# main.net
KiCad netlist of a schematic drawn in Altium Designer
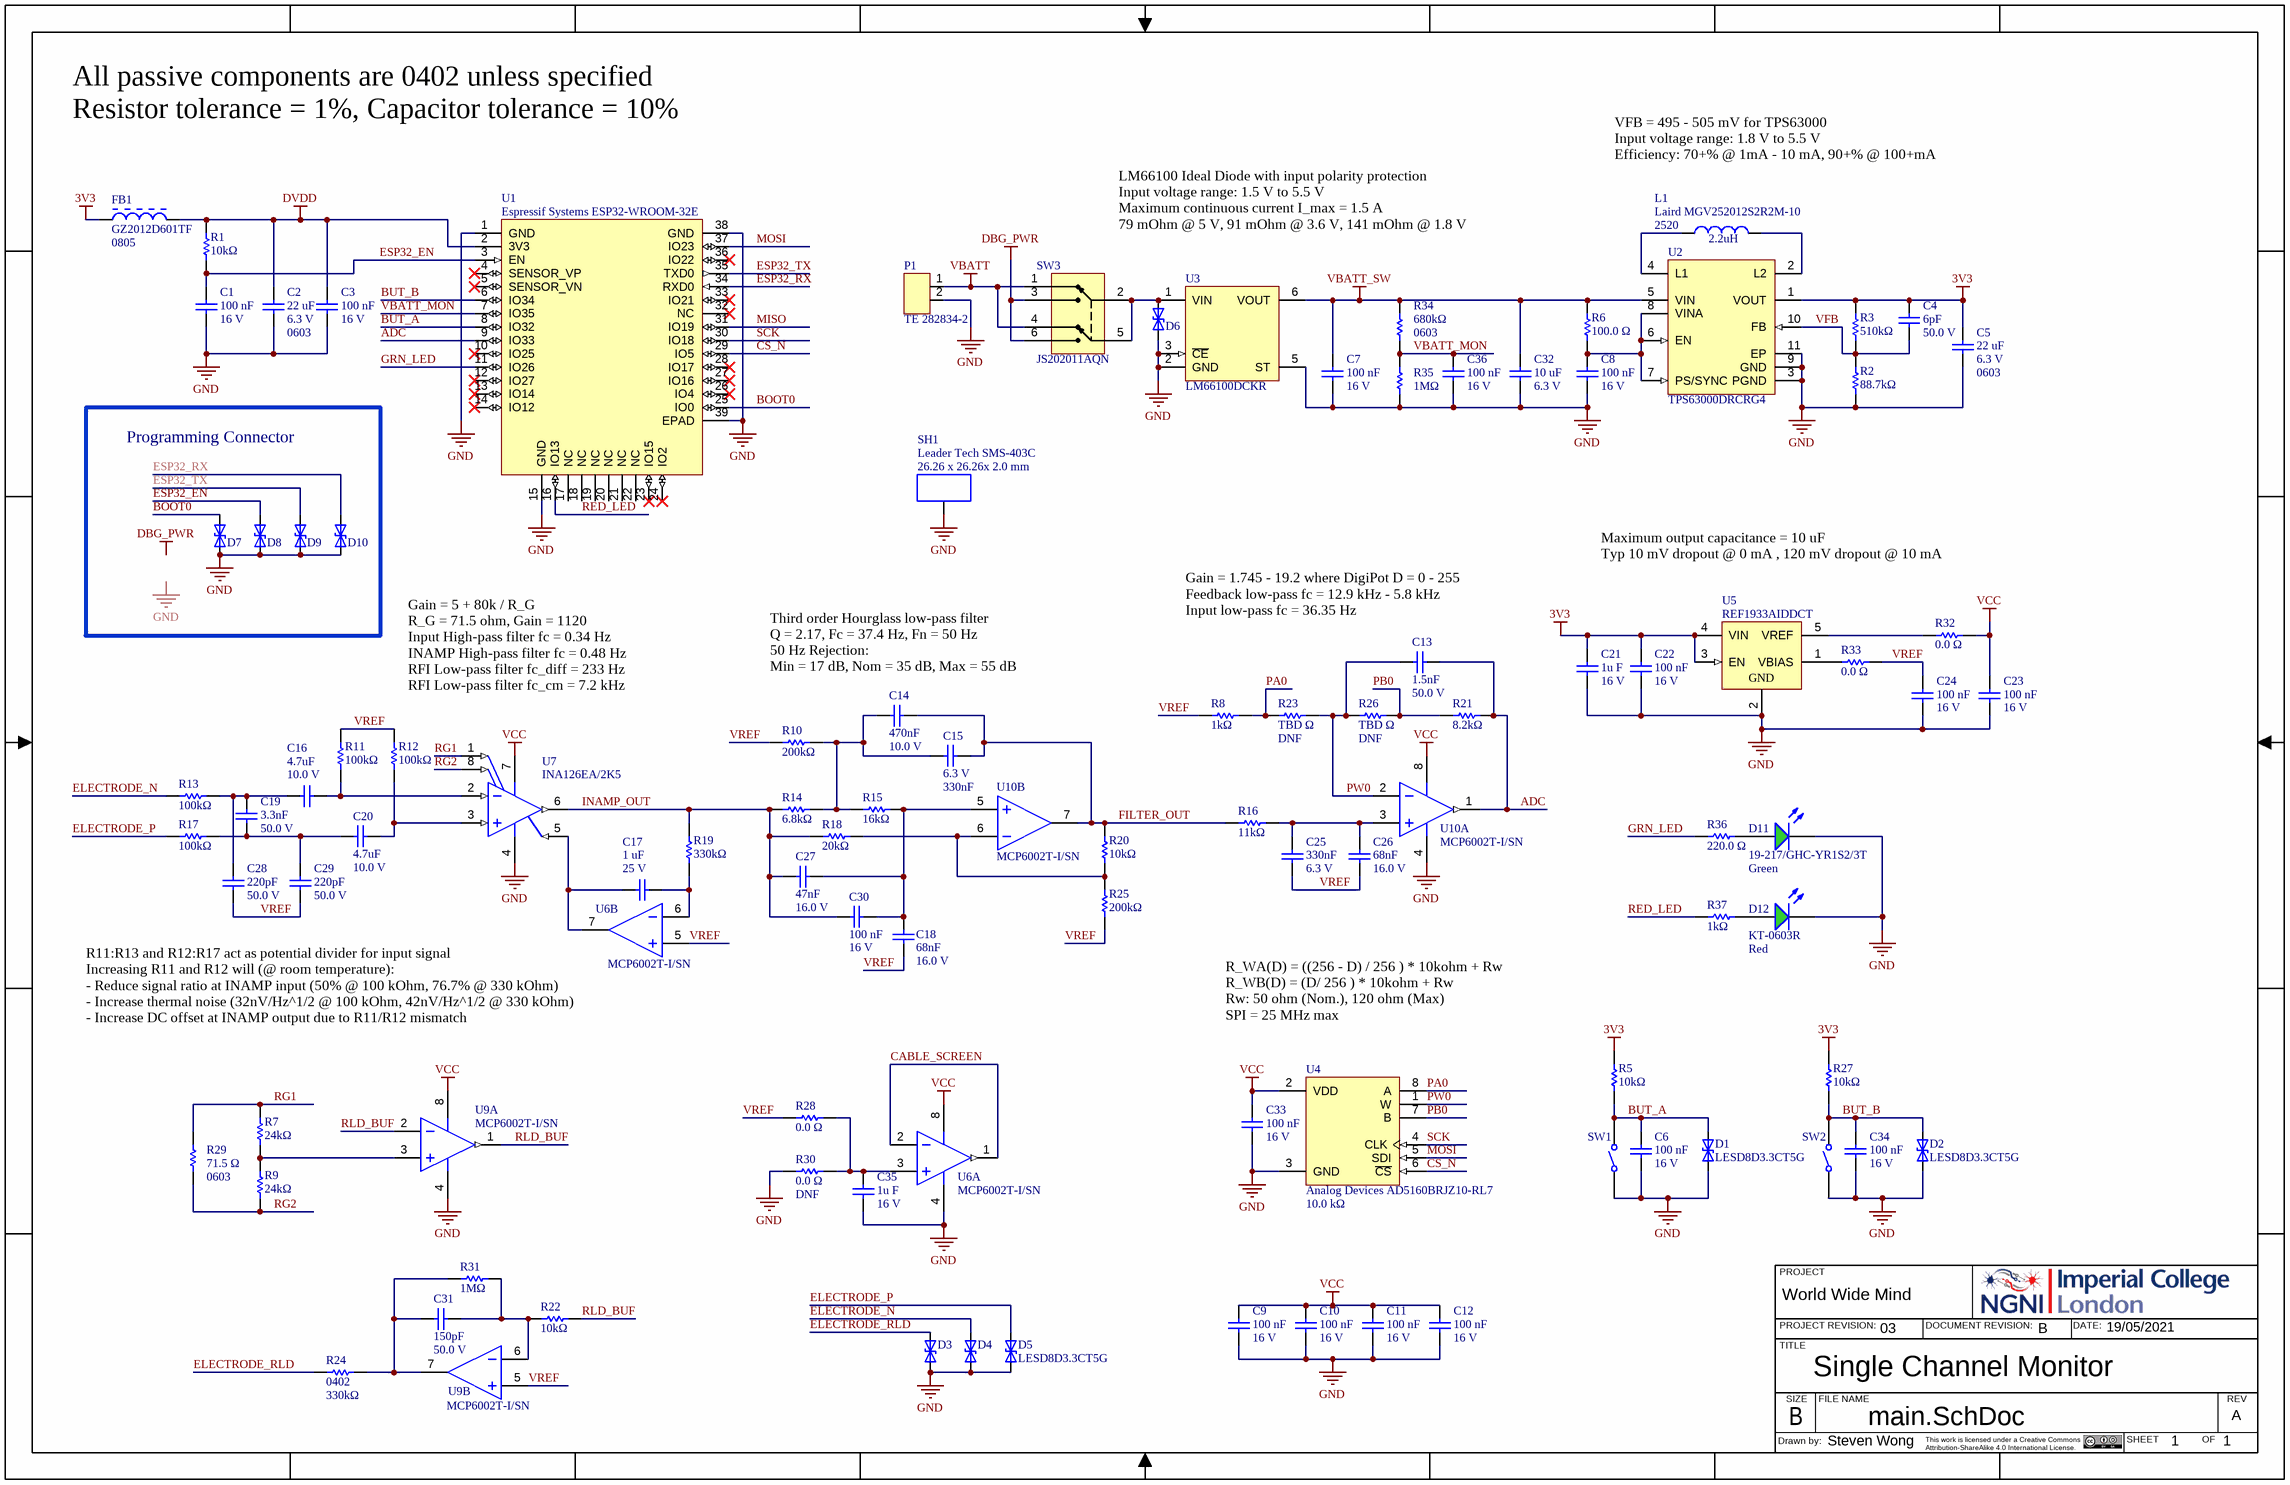
[diagram p0: main.SchDoc]

(export (version "E")
  (design (tool "Eeschema 10.0.6"))
  (components
    (comp (ref "C1")
      (value "100nF")
      (footprint "CAPC1005X56X25NL10T15")
      (description "Ceramic capacitor SMD-0402 100nF /16V X7R# K +-10%, Samsung, RoHS")
      (fields
        (field (name "CAPACITANCE") "100 nF")
        (field (name "VOLTAGE RATING") "16 V")
        (field (name "LCSC PART #") "C1525")
      )
      (libsource (lib "CommunityVault") (part "CMP-bf2276a55d9a60e5-19"))
    )
    (comp (ref "C2")
      (value "Murata GRM188R60G226MEA0L")
      (footprint "CAPC1608X90X35NL10T15")
      (description "Cap Ceramic 22uF 6.3V X5R 20% SMD 0603 85C Embossed T/R")
      (fields
        (field (name "CAPACITANCE") "22 uF")
        (field (name "VOLTAGE RATING (DC)") "6.3 V")
        (field (name "MANUFACTURER PART NUMBER") "GRM188R60G226MEA0L")
        (field (name "PACKAGE") "0603")
        (field (name "LCSC PART #") "C59461")
      )
      (libsource (lib "CommunityVault") (part "CMP-122043-3"))
    )
    (comp (ref "C3")
      (value "100nF")
      (footprint "CAPC1005X56X25NL10T15")
      (description "Ceramic capacitor SMD-0402 100nF /16V X7R# K +-10%, Samsung, RoHS")
      (fields
        (field (name "CAPACITANCE") "100 nF")
        (field (name "VOLTAGE RATING") "16 V")
        (field (name "LCSC PART #") "C1525")
      )
      (libsource (lib "CommunityVault") (part "CMP-bf2276a55d9a60e5-19"))
    )
    (comp (ref "C4")
      (value "AVX Interconnect / Elco 04025A6R0DAT2A")
      (footprint "CAPC1005X60X25NL10T15")
      (description "Multilayer Ceramic Capacitors MLCC - SMD/SMT 50volts 6pF C0G")
      (fields
        (field (name "CAPACITANCE") "6pF")
        (field (name "VOLTAGE RATING (DC)") "50.0 V")
        (field (name "MANUFACTURER PART NUMBER") "04025A6R0DAT2A")
        (field (name "LCSC PART #") "C30274")
      )
      (libsource (lib "CommunityVault") (part "CMP-173346-2"))
    )
    (comp (ref "C5")
      (value "Murata GRM188R60G226MEA0L")
      (footprint "CAPC1608X90X35NL10T15")
      (description "Cap Ceramic 22uF 6.3V X5R 20% SMD 0603 85C Embossed T/R")
      (fields
        (field (name "CAPACITANCE") "22 uF")
        (field (name "VOLTAGE RATING (DC)") "6.3 V")
        (field (name "MANUFACTURER PART NUMBER") "GRM188R60G226MEA0L")
        (field (name "PACKAGE") "0603")
        (field (name "LCSC PART #") "C59461")
      )
      (libsource (lib "CommunityVault") (part "CMP-122043-3"))
    )
    (comp (ref "C6")
      (value "100nF")
      (footprint "CAPC1005X56X25NL10T15")
      (description "Ceramic capacitor SMD-0402 100nF /16V X7R# K +-10%, Samsung, RoHS")
      (fields
        (field (name "CAPACITANCE") "100 nF")
        (field (name "VOLTAGE RATING") "16 V")
        (field (name "LCSC PART #") "C1525")
      )
      (libsource (lib "CommunityVault") (part "CMP-bf2276a55d9a60e5-19"))
    )
    (comp (ref "C7")
      (value "100nF")
      (footprint "CAPC1005X56X25NL10T15")
      (description "Ceramic capacitor SMD-0402 100nF /16V X7R# K +-10%, Samsung, RoHS")
      (fields
        (field (name "CAPACITANCE") "100 nF")
        (field (name "VOLTAGE RATING") "16 V")
        (field (name "LCSC PART #") "C1525")
      )
      (libsource (lib "CommunityVault") (part "CMP-bf2276a55d9a60e5-19"))
    )
    (comp (ref "C8")
      (value "100nF")
      (footprint "CAPC1005X56X25NL10T15")
      (description "Ceramic capacitor SMD-0402 100nF /16V X7R# K +-10%, Samsung, RoHS")
      (fields
        (field (name "CAPACITANCE") "100 nF")
        (field (name "VOLTAGE RATING") "16 V")
        (field (name "LCSC PART #") "C1525")
      )
      (libsource (lib "CommunityVault") (part "CMP-bf2276a55d9a60e5-19"))
    )
    (comp (ref "C9")
      (value "100nF")
      (footprint "CAPC1005X56X25NL10T15")
      (description "Ceramic capacitor SMD-0402 100nF /16V X7R# K +-10%, Samsung, RoHS")
      (fields
        (field (name "CAPACITANCE") "100 nF")
        (field (name "VOLTAGE RATING") "16 V")
        (field (name "LCSC PART #") "C1525")
      )
      (libsource (lib "CommunityVault") (part "CMP-bf2276a55d9a60e5-19"))
    )
    (comp (ref "C10")
      (value "100nF")
      (footprint "CAPC1005X56X25NL10T15")
      (description "Ceramic capacitor SMD-0402 100nF /16V X7R# K +-10%, Samsung, RoHS")
      (fields
        (field (name "CAPACITANCE") "100 nF")
        (field (name "VOLTAGE RATING") "16 V")
        (field (name "LCSC PART #") "C1525")
      )
      (libsource (lib "CommunityVault") (part "CMP-bf2276a55d9a60e5-19"))
    )
    (comp (ref "C11")
      (value "100nF")
      (footprint "CAPC1005X56X25NL10T15")
      (description "Ceramic capacitor SMD-0402 100nF /16V X7R# K +-10%, Samsung, RoHS")
      (fields
        (field (name "CAPACITANCE") "100 nF")
        (field (name "VOLTAGE RATING") "16 V")
        (field (name "LCSC PART #") "C1525")
      )
      (libsource (lib "CommunityVault") (part "CMP-bf2276a55d9a60e5-19"))
    )
    (comp (ref "C12")
      (value "100nF")
      (footprint "CAPC1005X56X25NL10T15")
      (description "Ceramic capacitor SMD-0402 100nF /16V X7R# K +-10%, Samsung, RoHS")
      (fields
        (field (name "CAPACITANCE") "100 nF")
        (field (name "VOLTAGE RATING") "16 V")
        (field (name "LCSC PART #") "C1525")
      )
      (libsource (lib "CommunityVault") (part "CMP-bf2276a55d9a60e5-19"))
    )
    (comp (ref "C13")
      (value "AVX Interconnect / Elco 04025C152KAT2A")
      (footprint "CAPC1005X56X25NL10T15")
      (description "Cap Ceramic 0.0015uF 50V X7R 10% SMD 0402 125C Paper T/R")
      (fields
        (field (name "MANUFACTURER PART NUMBER") "04025C152KAT2A")
        (field (name "CAPACITANCE") "1.5nF")
        (field (name "VOLTAGE RATING (DC)") "50.0 V")
        (field (name "LCSC PART #") "C23967")
      )
      (libsource (lib "CommunityVault") (part "CMP-126494-2"))
    )
    (comp (ref "C14")
      (value "AVX Interconnect / Elco 0402ZD474KAT2A")
      (footprint "CAPC1005X56X25NL10T15")
      (description "Multilayer Ceramic Capacitors MLCC - SMD/SMT 10volts 0.47uF 10% X5R")
      (fields
        (field (name "MANUFACTURER PART NUMBER") "0402ZD474KAT2A")
        (field (name "CAPACITANCE") "470nF")
        (field (name "VOLTAGE RATING (DC)") "10.0 V")
        (field (name "LCSC PART #") "C47339")
      )
      (libsource (lib "CommunityVault") (part "CMP-4106702-2"))
    )
    (comp (ref "C15")
      (value "CL05A334KQ5NNNC")
      (footprint "CAPC1005X55X25NL05T10")
      (description "CAP CER 0.33UF 10V 10% X5R 0402")
      (fields
        (field (name "VOLTAGE RATING (DC)") "6.3 V")
        (field (name "CAPACITANCE") "330nF")
        (field (name "LCSC PART #") "C307420")
      )
      (libsource (lib "CommunityVault") (part "CMP-119553-3"))
    )
    (comp (ref "C16")
      (value "CL05A475MP5NRNC")
      (footprint "CAPC1005X56X25NL10T15")
      (description "T&R / COMMERCIAL CHIP")
      (fields
        (field (name "CAPACITANCE") "4.7uF")
        (field (name "VOLTAGE RATING (DC)") "10.0 V")
        (field (name "LCSC PART #") "C23733")
      )
      (libsource (lib "CommunityVault") (part "CMP-19563753-2"))
    )
    (comp (ref "C17")
      (value "Samsung CL05A105KA5NQNC")
      (footprint "PCB-515da9ytrm2wahx6tw11-1")
      (description "Cap Ceramic 1uF 25V X5R 10% SMD 0402 85°C Cardboard T/R")
      (fields
        (field (name "VOLTAGE RATING (DC)") "25 V")
        (field (name "CAPACITANCE") "1 uF")
        (field (name "MANUFACTURER PART NUMBER") "CL05A105KA5NQNC")
        (field (name "LCSC PART #") "C52923")
      )
      (libsource (lib "CommunityVault") (part "CMP-8f214705328650e6-4"))
    )
    (comp (ref "C18")
      (value "Kemet C0402C683K4RACTU")
      (footprint "CAPC1005X55X30NL05T10")
      (description "CAP CER 0.068UF 16V 10% X7R 0402")
      (fields
        (field (name "CAPACITANCE") "68nF")
        (field (name "VOLTAGE RATING (DC)") "16.0 V")
        (field (name "MANUFACTURER PART NUMBER") "C0402C683K4RACTU")
        (field (name "LCSC PART #") "C12529")
      )
      (libsource (lib "CommunityVault") (part "CMP-124577-2"))
    )
    (comp (ref "C19")
      (value "AVX Interconnect / Elco 04025C332KAT2A")
      (footprint "CAPC1005X56X25NL10T15")
      (description "AVX   04025C332KAT2A   CAP, MLCC, X7R, 3.3NF, 50V, 0402")
      (fields
        (field (name "CAPACITANCE") "3.3nF")
        (field (name "VOLTAGE RATING (DC)") "50.0 V")
        (field (name "MANUFACTURER PART NUMBER") "04025C332KAT2A")
        (field (name "LCSC PART #") "C26404")
      )
      (libsource (lib "CommunityVault") (part "CMP-128367-2"))
    )
    (comp (ref "C20")
      (value "CL05A475MP5NRNC")
      (footprint "CAPC1005X56X25NL10T15")
      (description "T&R / COMMERCIAL CHIP")
      (fields
        (field (name "CAPACITANCE") "4.7uF")
        (field (name "VOLTAGE RATING (DC)") "10.0 V")
        (field (name "LCSC PART #") "C23733")
      )
      (libsource (lib "CommunityVault") (part "CMP-19563753-2"))
    )
    (comp (ref "C21")
      (value "Murata GRM155R61C105KA12D")
      (footprint "CAPC1005X55X25NL05T10")
      (description "Cap Ceramic 1uF 16V X5R 10% SMD 0402 85C Paper T/R")
      (fields
        (field (name "CAPACITANCE") "1u F")
        (field (name "VOLTAGE RATING (DC)") "16 V")
        (field (name "MANUFACTURER PART NUMBER") "GRM155R61C105KA12D")
        (field (name "LCSC PART #") "C52923")
      )
      (libsource (lib "CommunityVault") (part "CMP-7562325-2"))
    )
    (comp (ref "C22")
      (value "100nF")
      (footprint "CAPC1005X56X25NL10T15")
      (description "Ceramic capacitor SMD-0402 100nF /16V X7R# K +-10%, Samsung, RoHS")
      (fields
        (field (name "CAPACITANCE") "100 nF")
        (field (name "VOLTAGE RATING") "16 V")
        (field (name "LCSC PART #") "C1525")
      )
      (libsource (lib "CommunityVault") (part "CMP-bf2276a55d9a60e5-19"))
    )
    (comp (ref "C23")
      (value "100nF")
      (footprint "CAPC1005X56X25NL10T15")
      (description "Ceramic capacitor SMD-0402 100nF /16V X7R# K +-10%, Samsung, RoHS")
      (fields
        (field (name "CAPACITANCE") "100 nF")
        (field (name "VOLTAGE RATING") "16 V")
        (field (name "LCSC PART #") "C1525")
      )
      (libsource (lib "CommunityVault") (part "CMP-bf2276a55d9a60e5-19"))
    )
    (comp (ref "C24")
      (value "100nF")
      (footprint "CAPC1005X56X25NL10T15")
      (description "Ceramic capacitor SMD-0402 100nF /16V X7R# K +-10%, Samsung, RoHS")
      (fields
        (field (name "CAPACITANCE") "100 nF")
        (field (name "VOLTAGE RATING") "16 V")
        (field (name "LCSC PART #") "C1525")
      )
      (libsource (lib "CommunityVault") (part "CMP-bf2276a55d9a60e5-19"))
    )
    (comp (ref "C25")
      (value "CL05A334KQ5NNNC")
      (footprint "CAPC1005X55X25NL05T10")
      (description "CAP CER 0.33UF 10V 10% X5R 0402")
      (fields
        (field (name "VOLTAGE RATING (DC)") "6.3 V")
        (field (name "CAPACITANCE") "330nF")
        (field (name "LCSC PART #") "C307420")
      )
      (libsource (lib "CommunityVault") (part "CMP-119553-3"))
    )
    (comp (ref "C26")
      (value "Kemet C0402C683K4RACTU")
      (footprint "CAPC1005X55X30NL05T10")
      (description "CAP CER 0.068UF 16V 10% X7R 0402")
      (fields
        (field (name "CAPACITANCE") "68nF")
        (field (name "VOLTAGE RATING (DC)") "16.0 V")
        (field (name "MANUFACTURER PART NUMBER") "C0402C683K4RACTU")
        (field (name "LCSC PART #") "C12529")
      )
      (libsource (lib "CommunityVault") (part "CMP-124577-2"))
    )
    (comp (ref "C27")
      (value "AVX Interconnect / Elco 04023C473KAT2A")
      (footprint "CAPC1005X56X25NL10T15")
      (description "Multilayer Ceramic Capacitors MLCC - SMD/SMT 25volts 0.047uF 10% X7R 0402 SIZE")
      (fields
        (field (name "CAPACITANCE") "47nF")
        (field (name "VOLTAGE RATING (DC)") "16.0 V")
        (field (name "MANUFACTURER PART NUMBER") "04023C473KAT2A")
        (field (name "LCSC PART #") "C26403")
      )
      (libsource (lib "CommunityVault") (part "CMP-8988077-2"))
    )
    (comp (ref "C28")
      (value "Kemet C0402C221K5RACAUTO")
      (footprint "CAPC1005X55X30NL05T10")
      (description "CAPACITOR, 0402, X7R, 50V, 220PF")
      (fields
        (field (name "MANUFACTURER PART NUMBER") "C0402C221K5RACAUTO")
        (field (name "CAPACITANCE") "220pF")
        (field (name "VOLTAGE RATING (DC)") "50.0 V")
        (field (name "LCSC PART #") "C1530")
      )
      (libsource (lib "CommunityVault") (part "CMP-3913259-2"))
    )
    (comp (ref "C29")
      (value "Kemet C0402C221K5RACAUTO")
      (footprint "CAPC1005X55X30NL05T10")
      (description "CAPACITOR, 0402, X7R, 50V, 220PF")
      (fields
        (field (name "MANUFACTURER PART NUMBER") "C0402C221K5RACAUTO")
        (field (name "CAPACITANCE") "220pF")
        (field (name "VOLTAGE RATING (DC)") "50.0 V")
        (field (name "LCSC PART #") "C1530")
      )
      (libsource (lib "CommunityVault") (part "CMP-3913259-2"))
    )
    (comp (ref "C30")
      (value "100nF")
      (footprint "CAPC1005X56X25NL10T15")
      (description "Ceramic capacitor SMD-0402 100nF /16V X7R# K +-10%, Samsung, RoHS")
      (fields
        (field (name "CAPACITANCE") "100 nF")
        (field (name "VOLTAGE RATING") "16 V")
        (field (name "LCSC PART #") "C1525")
      )
      (libsource (lib "CommunityVault") (part "CMP-bf2276a55d9a60e5-19"))
    )
    (comp (ref "C31")
      (value "AVX Interconnect / Elco 04025A151JAT2A")
      (footprint "CAPC1005X56X25NL10T15")
      (description "AVX   04025A151JAT2A   CAP, MLCC, C0G/NP0, 150PF, 50V, 0402")
      (fields
        (field (name "CAPACITANCE") "150pF")
        (field (name "VOLTAGE RATING (DC)") "50.0 V")
        (field (name "MANUFACTURER PART NUMBER") "04025A151JAT2A")
        (field (name "LCSC PART #") "C1527")
      )
      (libsource (lib "CommunityVault") (part "CMP-128358-2"))
    )
    (comp (ref "C32")
      (value "Samsung CL05A106MQ5NUNC")
      (footprint "PCB-a41llqp6xpt8gy62f2hk-1")
      (description "Cap Ceramic 10uF 6.3V X5R 20% SMD 0402 85°C Paper T/R")
      (fields
        (field (name "MANUFACTURER PART NUMBER") "CL05A106MQ5NUNC")
        (field (name "VOLTAGE RATING (DC)") "6.3 V")
        (field (name "CAPACITANCE") "10 uF")
        (field (name "LCSC PART #") "C15525")
      )
      (libsource (lib "CommunityVault") (part "CMP-fd5e350784e62299-2"))
    )
    (comp (ref "C33")
      (value "100nF")
      (footprint "CAPC1005X56X25NL10T15")
      (description "Ceramic capacitor SMD-0402 100nF /16V X7R# K +-10%, Samsung, RoHS")
      (fields
        (field (name "CAPACITANCE") "100 nF")
        (field (name "VOLTAGE RATING") "16 V")
        (field (name "LCSC PART #") "C1525")
      )
      (libsource (lib "CommunityVault") (part "CMP-bf2276a55d9a60e5-19"))
    )
    (comp (ref "C34")
      (value "100nF")
      (footprint "CAPC1005X56X25NL10T15")
      (description "Ceramic capacitor SMD-0402 100nF /16V X7R# K +-10%, Samsung, RoHS")
      (fields
        (field (name "CAPACITANCE") "100 nF")
        (field (name "VOLTAGE RATING") "16 V")
        (field (name "LCSC PART #") "C1525")
      )
      (libsource (lib "CommunityVault") (part "CMP-bf2276a55d9a60e5-19"))
    )
    (comp (ref "C35")
      (value "Murata GRM155R61C105KA12D")
      (footprint "CAPC1005X55X25NL05T10")
      (description "Cap Ceramic 1uF 16V X5R 10% SMD 0402 85C Paper T/R")
      (fields
        (field (name "CAPACITANCE") "1u F")
        (field (name "VOLTAGE RATING (DC)") "16 V")
        (field (name "MANUFACTURER PART NUMBER") "GRM155R61C105KA12D")
        (field (name "LCSC PART #") "C52923")
      )
      (libsource (lib "CommunityVault") (part "CMP-7562325-2"))
    )
    (comp (ref "C36")
      (value "100nF")
      (footprint "CAPC1005X56X25NL10T15")
      (description "Ceramic capacitor SMD-0402 100nF /16V X7R# K +-10%, Samsung, RoHS")
      (fields
        (field (name "CAPACITANCE") "100 nF")
        (field (name "VOLTAGE RATING") "16 V")
        (field (name "LCSC PART #") "C1525")
      )
      (libsource (lib "CommunityVault") (part "CMP-bf2276a55d9a60e5-19"))
    )
    (comp (ref "D1")
      (value "LESD8D3.3CT5G")
      (footprint "DFN64P100X50-2N")
      (description "Bidirectional 3.3V (Max) 5V 14.1V 11.2A(8/20us) SOD-882 Diodes - ESD RoHS")
      (fields (field (name "MANUFACTURER") "LRC") (field (name "LCSC PART #") "C172410"))
      (libsource (lib "FavoritesLibrary") (part "SYM-zjatvudan2pmebzuzrjd-1"))
    )
    (comp (ref "D2")
      (value "LESD8D3.3CT5G")
      (footprint "DFN64P100X50-2N")
      (description "Bidirectional 3.3V (Max) 5V 14.1V 11.2A(8/20us) SOD-882 Diodes - ESD RoHS")
      (fields (field (name "MANUFACTURER") "LRC") (field (name "LCSC PART #") "C172410"))
      (libsource (lib "FavoritesLibrary") (part "SYM-zjatvudan2pmebzuzrjd-1"))
    )
    (comp (ref "D3")
      (value "LESD8D3.3CT5G")
      (footprint "DFN64P100X50-2N")
      (description "Bidirectional 3.3V (Max) 5V 14.1V 11.2A(8/20us) SOD-882 Diodes - ESD RoHS")
      (fields (field (name "MANUFACTURER") "LRC") (field (name "LCSC PART #") "C172410"))
      (libsource (lib "FavoritesLibrary") (part "SYM-zjatvudan2pmebzuzrjd-1"))
    )
    (comp (ref "D4")
      (value "LESD8D3.3CT5G")
      (footprint "DFN64P100X50-2N")
      (description "Bidirectional 3.3V (Max) 5V 14.1V 11.2A(8/20us) SOD-882 Diodes - ESD RoHS")
      (fields (field (name "MANUFACTURER") "LRC") (field (name "LCSC PART #") "C172410"))
      (libsource (lib "FavoritesLibrary") (part "SYM-zjatvudan2pmebzuzrjd-1"))
    )
    (comp (ref "D5")
      (value "LESD8D3.3CT5G")
      (footprint "DFN64P100X50-2N")
      (description "Bidirectional 3.3V (Max) 5V 14.1V 11.2A(8/20us) SOD-882 Diodes - ESD RoHS")
      (fields (field (name "MANUFACTURER") "LRC") (field (name "LCSC PART #") "C172410"))
      (libsource (lib "FavoritesLibrary") (part "SYM-zjatvudan2pmebzuzrjd-1"))
    )
    (comp (ref "D6")
      (value "LESD8D3.3CT5G")
      (footprint "DFN64P100X50-2N")
      (description "Bidirectional 3.3V (Max) 5V 14.1V 11.2A(8/20us) SOD-882 Diodes - ESD RoHS")
      (fields (field (name "MANUFACTURER") "LRC") (field (name "LCSC PART #") "C172410"))
      (libsource (lib "FavoritesLibrary") (part "SYM-zjatvudan2pmebzuzrjd-1"))
    )
    (comp (ref "D7")
      (value "LESD8D3.3CT5G")
      (footprint "DFN64P100X50-2N")
      (description "Bidirectional 3.3V (Max) 5V 14.1V 11.2A(8/20us) SOD-882 Diodes - ESD RoHS")
      (fields (field (name "MANUFACTURER") "LRC") (field (name "LCSC PART #") "C172410"))
      (libsource (lib "FavoritesLibrary") (part "SYM-zjatvudan2pmebzuzrjd-1"))
    )
    (comp (ref "D8")
      (value "LESD8D3.3CT5G")
      (footprint "DFN64P100X50-2N")
      (description "Bidirectional 3.3V (Max) 5V 14.1V 11.2A(8/20us) SOD-882 Diodes - ESD RoHS")
      (fields (field (name "MANUFACTURER") "LRC") (field (name "LCSC PART #") "C172410"))
      (libsource (lib "FavoritesLibrary") (part "SYM-zjatvudan2pmebzuzrjd-1"))
    )
    (comp (ref "D9")
      (value "LESD8D3.3CT5G")
      (footprint "DFN64P100X50-2N")
      (description "Bidirectional 3.3V (Max) 5V 14.1V 11.2A(8/20us) SOD-882 Diodes - ESD RoHS")
      (fields (field (name "MANUFACTURER") "LRC") (field (name "LCSC PART #") "C172410"))
      (libsource (lib "FavoritesLibrary") (part "SYM-zjatvudan2pmebzuzrjd-1"))
    )
    (comp (ref "D10")
      (value "LESD8D3.3CT5G")
      (footprint "DFN64P100X50-2N")
      (description "Bidirectional 3.3V (Max) 5V 14.1V 11.2A(8/20us) SOD-882 Diodes - ESD RoHS")
      (fields (field (name "MANUFACTURER") "LRC") (field (name "LCSC PART #") "C172410"))
      (libsource (lib "FavoritesLibrary") (part "SYM-zjatvudan2pmebzuzrjd-1"))
    )
    (comp (ref "D11")
      (value "19-217/GHC-YR1S2/3T")
      (footprint "PCB-qrh50x9m6cshxb6d9t7t-1")
      (description "LED SMD Top View Uni-Color Brilliant Green 518nm 0603 Pkg ø7T/R 3k\"")
      (fields (field (name "LCSC PART #") "C72043") (field (name "COLOUR") "Green"))
      (libsource (lib "CommunityVault") (part "CMP-7093b92408b7af54-1"))
    )
    (comp (ref "D12")
      (value "KT-0603R")
      (footprint "PCB-qrh50x9m6cshxb6d9t7t-1")
      (description "LED SMD Top View Uni-Color Brilliant Green 518nm 0603 Pkg ø7T/R 3k\"")
      (fields (field (name "LCSC PART #") "C2286") (field (name "COLOUR") "Red"))
      (libsource (lib "CommunityVault") (part "CMP-7093b92408b7af54-1"))
    )
    (comp (ref "FB1")
      (value "GZ2012D601TF")
      (footprint "MURA-BLM21-H1-CHIP-2_V")
      (fields
        (field (name "CASE/PACKAGE") "0805")
        (field (name "MANUFACTURER PART NUMBER") "BLM21BB331SN1D")
        (field (name "LCSC PART #") "C1017")
      )
      (libsource (lib "CommunityVault") (part "CMP-887293-3"))
    )
    (comp (ref "L1")
      (value "Laird MGV252012S2R2M-10")
      (footprint "INDM2520X12N")
      (description "MGV252012 - High Current Molded SMT Power Inductor")
      (fields
        (field (name "MANUFACTURER PART NUMBER") "MGV252012S2R2M-10")
        (field (name "LCSC PART #") "C375952")
        (field (name "INDUCTANCE") "2.2uH")
        (field (name "PACKAGE") "2520")
      )
      (libsource (lib "CommunityVault") (part "CMP-6756ab2d39beb891-1"))
    )
    (comp (ref "P1")
      (value "TE 282834-2")
      (footprint "PCB-6xrngco598u3mra2uzi2-1")
      (description "Wire-To-Board Terminal Block, 2, 150 V, 10 A, 30 Awg, 16 Awg, 1.4 Mm")
      (libsource (lib "CommunityVault") (part "SYM-4e52859dc8429195-14"))
    )
    (comp (ref "R1")
      (value "Yageo / Phycomp RC0402FR-1310KL")
      (footprint "RESC1005X40X25NL05T10")
      (description "Thick Film Resistors - SMD 10K OHM 1%")
      (fields
        (field (name "RESISTANCE") "10kΩ")
        (field (name "MANUFACTURER PART NUMBER") "RC0402FR-1310KL")
        (field (name "LCSC PART #") "C25744")
      )
      (libsource (lib "CommunityVault") (part "CMP-3661304-2"))
    )
    (comp (ref "R2")
      (value "Panasonic ERJ-2RKF8872X")
      (footprint "RESC1005X40X25NL05T05")
      (description "Thick Film Resistors - SMD 0402 88.7Kohms 1% Tol")
      (fields
        (field (name "RESISTANCE") "88.7kΩ")
        (field (name "MANUFACTURER PART NUMBER") "ERJ-2RKF8872X")
        (field (name "LCSC PART #") "C25922")
      )
      (libsource (lib "CommunityVault") (part "CMP-3682312-2"))
    )
    (comp (ref "R3")
      (value "Vishay Dale CRCW0402510KFKED")
      (footprint "RESC1005X40X25NL05T05")
      (description "RES SMD 510K OHM 1% 1/16W 0402")
      (fields
        (field (name "RESISTANCE") "510kΩ")
        (field (name "MANUFACTURER PART NUMBER") "CRCW0402510KFKED")
        (field (name "LCSC PART #") "C11616")
      )
      (libsource (lib "CommunityVault") (part "CMP-3945506-8"))
    )
    (comp (ref "R5")
      (value "Yageo / Phycomp RC0402FR-1310KL")
      (footprint "RESC1005X40X25NL05T10")
      (description "Thick Film Resistors - SMD 10K OHM 1%")
      (fields
        (field (name "RESISTANCE") "10kΩ")
        (field (name "MANUFACTURER PART NUMBER") "RC0402FR-1310KL")
        (field (name "LCSC PART #") "C25744")
      )
      (libsource (lib "CommunityVault") (part "CMP-3661304-2"))
    )
    (comp (ref "R6")
      (value "Yageo RC0402FR-13100RL")
      (footprint "RESC1005X40X25NL05T10")
      (description "YAGEO   RC0402FR-13100RL   THICK FILM RESISTOR, 100 OHM, 62.5mW, 1%")
      (fields
        (field (name "RESISTANCE") "100.0 Ω")
        (field (name "MANUFACTURER PART NUMBER") "RC0402FR-13100RL")
        (field (name "LCSC PART #") "C25076")
      )
      (libsource (lib "CommunityVault") (part "CMP-3765204-2"))
    )
    (comp (ref "R7")
      (value "Yageo / Phycomp RC0402FR-0724KL")
      (footprint "RESC1005X40X25NL05T10")
      (description "RESISTOR, 0402 0.063W 1% 24K")
      (fields
        (field (name "MANUFACTURER PART NUMBER") "RC0402FR-0724KL")
        (field (name "RESISTANCE") "24kΩ")
        (field (name "LCSC PART #") "C25769")
      )
      (libsource (lib "CommunityVault") (part "CMP-1900184-2"))
    )
    (comp (ref "R8")
      (value "KOA Speer RK73H1ETTP1001F")
      (footprint "RESC1005X40X25NL10T10")
      (description "Res Thick Film 0402 1K Ohm 1% 0.063W(1/16W) ±100ppm/C Molded SMD Automotive Punched Paper T/R")
      (fields
        (field (name "RESISTANCE") "1kΩ")
        (field (name "MANUFACTURER PART NUMBER") "RK73H1ETTP1001F")
        (field (name "LCSC PART #") "C11702")
      )
      (libsource (lib "CommunityVault") (part "CMP-2823544-2"))
    )
    (comp (ref "R9")
      (value "Yageo / Phycomp RC0402FR-0724KL")
      (footprint "RESC1005X40X25NL05T10")
      (description "RESISTOR, 0402 0.063W 1% 24K")
      (fields
        (field (name "MANUFACTURER PART NUMBER") "RC0402FR-0724KL")
        (field (name "RESISTANCE") "24kΩ")
        (field (name "LCSC PART #") "C25769")
      )
      (libsource (lib "CommunityVault") (part "CMP-1900184-2"))
    )
    (comp (ref "R10")
      (value "KOA Speer RK73H1ETTP2003F")
      (footprint "RESC1005X40X25NL10T10")
      (description "Res Thick Film 0402 200K Ohm 1% 0.063W(1/16W) ±100ppm/C Molded SMD Automotive Punched Paper T/R")
      (fields
        (field (name "MANUFACTURER PART NUMBER") "RK73H1ETTP2003F")
        (field (name "RESISTANCE") "200kΩ")
        (field (name "LCSC PART #") "C25764")
      )
      (libsource (lib "CommunityVault") (part "CMP-2823564-2"))
    )
    (comp (ref "R11")
      (value "Yageo RC0402FR-13100KL")
      (footprint "RESC1005X40X25NL05T10")
      (description "YAGEO   RC0402FR-13100KL   THICK FILM RESISTOR, 100KOHM, 62.5mW 1%")
      (fields
        (field (name "MANUFACTURER PART NUMBER") "RC0402FR-13100KL")
        (field (name "RESISTANCE") "100kΩ")
        (field (name "LCSC PART #") "C25741")
      )
      (libsource (lib "CommunityVault") (part "CMP-3759242-3"))
    )
    (comp (ref "R12")
      (value "Yageo RC0402FR-13100KL")
      (footprint "RESC1005X40X25NL05T10")
      (description "YAGEO   RC0402FR-13100KL   THICK FILM RESISTOR, 100KOHM, 62.5mW 1%")
      (fields
        (field (name "MANUFACTURER PART NUMBER") "RC0402FR-13100KL")
        (field (name "RESISTANCE") "100kΩ")
        (field (name "LCSC PART #") "C25741")
      )
      (libsource (lib "CommunityVault") (part "CMP-3759242-3"))
    )
    (comp (ref "R13")
      (value "Yageo RC0402FR-13100KL")
      (footprint "RESC1005X40X25NL05T10")
      (description "YAGEO   RC0402FR-13100KL   THICK FILM RESISTOR, 100KOHM, 62.5mW 1%")
      (fields
        (field (name "MANUFACTURER PART NUMBER") "RC0402FR-13100KL")
        (field (name "RESISTANCE") "100kΩ")
        (field (name "LCSC PART #") "C25741")
      )
      (libsource (lib "CommunityVault") (part "CMP-3759242-3"))
    )
    (comp (ref "R14")
      (value "Vishay Dale CRCW04026K80FKED")
      (footprint "RESC1005X40X25NL05T05")
      (description "RES SMD 6.8K OHM 1% 1/16W 0402")
      (fields
        (field (name "RESISTANCE") "6.8kΩ")
        (field (name "MANUFACTURER PART NUMBER") "CRCW04026K80FKED")
        (field (name "LCSC PART #") "C25917")
      )
      (libsource (lib "CommunityVault") (part "CMP-1856508-2"))
    )
    (comp (ref "R15")
      (value "Yageo / Phycomp RC0402FR-0716KL")
      (footprint "RESC1005X40X25NL05T10")
      (description "YAGEO (PHYCOMP)   RC0402FR-0716KL   RESISTOR, 0402 0.063W 1% 16K")
      (fields
        (field (name "MANUFACTURER PART NUMBER") "RC0402FR-0716KL")
        (field (name "RESISTANCE") "16kΩ")
        (field (name "LCSC PART #") "C25759")
      )
      (libsource (lib "CommunityVault") (part "CMP-1853199-2"))
    )
    (comp (ref "R16")
      (value "Yageo / Phycomp RC0402FR-0711KL")
      (footprint "RESC1005X40X25NL05T10")
      (description "RES SMD 11K OHM 1% 1/16W 0402")
      (fields
        (field (name "RESISTANCE") "11kΩ")
        (field (name "MANUFACTURER PART NUMBER") "RC0402FR-0711KL")
        (field (name "LCSC PART #") "C25749")
      )
      (libsource (lib "CommunityVault") (part "CMP-1853185-2"))
    )
    (comp (ref "R17")
      (value "Yageo RC0402FR-13100KL")
      (footprint "RESC1005X40X25NL05T10")
      (description "YAGEO   RC0402FR-13100KL   THICK FILM RESISTOR, 100KOHM, 62.5mW 1%")
      (fields
        (field (name "MANUFACTURER PART NUMBER") "RC0402FR-13100KL")
        (field (name "RESISTANCE") "100kΩ")
        (field (name "LCSC PART #") "C25741")
      )
      (libsource (lib "CommunityVault") (part "CMP-3759242-3"))
    )
    (comp (ref "R18")
      (value "Panasonic ERJ-2RKF2002X")
      (footprint "RESC1005X40X25NL05T05")
      (description "Thick Film Resistors - SMD 0402 20Kohms 1% Tol")
      (fields
        (field (name "RESISTANCE") "20kΩ")
        (field (name "MANUFACTURER PART NUMBER") "ERJ-2RKF2002X")
        (field (name "LCSC PART #") "C25765")
      )
      (libsource (lib "CommunityVault") (part "CMP-3656287-2"))
    )
    (comp (ref "R19")
      (value "Vishay Dale CRCW0402330KFKED")
      (footprint "RESC1005X40X25NL05T05")
      (description "RES SMD 330K OHM 1% 1/16W 0402")
      (fields
        (field (name "RESISTANCE") "330kΩ")
        (field (name "MANUFACTURER PART NUMBER") "CRCW0402330KFKED")
        (field (name "LCSC PART #") "C25778")
      )
      (libsource (lib "CommunityVault") (part "CMP-1856416-2"))
    )
    (comp (ref "R20")
      (value "Yageo / Phycomp RC0402FR-1310KL")
      (footprint "RESC1005X40X25NL05T10")
      (description "Thick Film Resistors - SMD 10K OHM 1%")
      (fields
        (field (name "RESISTANCE") "10kΩ")
        (field (name "MANUFACTURER PART NUMBER") "RC0402FR-1310KL")
        (field (name "LCSC PART #") "C25744")
      )
      (libsource (lib "CommunityVault") (part "CMP-3661304-2"))
    )
    (comp (ref "R21")
      (value "Yageo AC0402FR-078K2L")
      (footprint "RESC1005X37X25NL05T10")
      (description "0402 8.2k ohms 1% automotive grade chip resistor")
      (fields
        (field (name "MANUFACTURER PART NUMBER") "AC0402FR-078K2L")
        (field (name "RESISTANCE") "8.2kΩ")
        (field (name "LCSC PART #") "C25924")
      )
      (libsource (lib "CommunityVault") (part "CMP-9399996-2"))
    )
    (comp (ref "R22")
      (value "Yageo / Phycomp RC0402FR-1310KL")
      (footprint "RESC1005X40X25NL05T10")
      (description "Thick Film Resistors - SMD 10K OHM 1%")
      (fields
        (field (name "RESISTANCE") "10kΩ")
        (field (name "MANUFACTURER PART NUMBER") "RC0402FR-1310KL")
        (field (name "LCSC PART #") "C25744")
      )
      (libsource (lib "CommunityVault") (part "CMP-3661304-2"))
    )
    (comp (ref "R23")
      (value "Yageo / Phycomp RC0402FR-1310KL")
      (footprint "RESC1005X40X25NL05T10")
      (description "Thick Film Resistors - SMD 10K OHM 1%")
      (fields
        (field (name "RESISTANCE") "TBD Ω")
        (field (name "MANUFACTURER PART NUMBER") "RC0402FR-1310KL")
        (field (name "FIT") "DNF")
        (field (name "LCSC PART #") "C25744")
      )
      (libsource (lib "CommunityVault") (part "CMP-3661304-2"))
    )
    (comp (ref "R24")
      (value "Vishay Dale CRCW0402330KFKED")
      (footprint "RESC1005X40X25NL05T05")
      (description "RES SMD 330K OHM 1% 1/16W 0402")
      (fields
        (field (name "CASE/PACKAGE") "0402")
        (field (name "RESISTANCE") "330kΩ")
        (field (name "MANUFACTURER PART NUMBER") "CRCW0402330KFKED")
        (field (name "LCSC PART #") "C25778")
      )
      (libsource (lib "CommunityVault") (part "CMP-1856416-2"))
    )
    (comp (ref "R25")
      (value "KOA Speer RK73H1ETTP2003F")
      (footprint "RESC1005X40X25NL10T10")
      (description "Res Thick Film 0402 200K Ohm 1% 0.063W(1/16W) ±100ppm/C Molded SMD Automotive Punched Paper T/R")
      (fields
        (field (name "MANUFACTURER PART NUMBER") "RK73H1ETTP2003F")
        (field (name "RESISTANCE") "200kΩ")
        (field (name "LCSC PART #") "C25764")
      )
      (libsource (lib "CommunityVault") (part "CMP-2823564-2"))
    )
    (comp (ref "R26")
      (value "Yageo / Phycomp RC0402FR-1310KL")
      (footprint "RESC1005X40X25NL05T10")
      (description "Thick Film Resistors - SMD 10K OHM 1%")
      (fields
        (field (name "RESISTANCE") "TBD Ω")
        (field (name "MANUFACTURER PART NUMBER") "RC0402FR-1310KL")
        (field (name "FIT") "DNF")
        (field (name "LCSC PART #") "C25744")
      )
      (libsource (lib "CommunityVault") (part "CMP-3661304-2"))
    )
    (comp (ref "R27")
      (value "Yageo / Phycomp RC0402FR-1310KL")
      (footprint "RESC1005X40X25NL05T10")
      (description "Thick Film Resistors - SMD 10K OHM 1%")
      (fields
        (field (name "RESISTANCE") "10kΩ")
        (field (name "MANUFACTURER PART NUMBER") "RC0402FR-1310KL")
        (field (name "LCSC PART #") "C25744")
      )
      (libsource (lib "CommunityVault") (part "CMP-3661304-2"))
    )
    (comp (ref "R28")
      (value "Yageo AC0402JR-070RL")
      (footprint "RESC1005X37X25NL05T10")
      (description "RES SMD 0.0 OHM JUMPER 1/16W")
      (fields
        (field (name "MANUFACTURER PART NUMBER") "AC0402JR-070RL")
        (field (name "RESISTANCE") "0.0 Ω")
        (field (name "LCSC PART #") "C17168")
      )
      (libsource (lib "CommunityVault") (part "CMP-1900348-2"))
    )
    (comp (ref "R29")
      (value "Panasonic ERJ-3EKF71R5V")
      (footprint "RESC1608X55X30NL15T15")
      (description "Thick Film Resistors - SMD 0603 71.5ohms 1% Tol")
      (fields
        (field (name "CASE/PACKAGE") "0603")
        (field (name "RESISTANCE") "71.5 Ω")
        (field (name "MANUFACTURER PART NUMBER") "ERJ-3EKF71R5V")
        (field (name "LCSC PART #") "C23104")
      )
      (libsource (lib "CommunityVault") (part "CMP-3679617-2"))
    )
    (comp (ref "R30")
      (value "Yageo AC0402JR-070RL")
      (footprint "RESC1005X37X25NL05T10")
      (description "RES SMD 0.0 OHM JUMPER 1/16W")
      (fields
        (field (name "MANUFACTURER PART NUMBER") "AC0402JR-070RL")
        (field (name "RESISTANCE") "0.0 Ω")
        (field (name "LCSC PART #") "C17168")
        (field (name "FIT") "DNF")
      )
      (libsource (lib "CommunityVault") (part "CMP-1900348-2"))
    )
    (comp (ref "R31")
      (value "Yageo AC0402FR-071ML")
      (footprint "RESC1005X37X25NL05T10")
      (description "Thick Film Resistors 1/16W 1M ohm 1%")
      (fields
        (field (name "MANUFACTURER PART NUMBER") "AC0402FR-071ML")
        (field (name "RESISTANCE") "1MΩ")
        (field (name "LCSC PART #") "C26083")
      )
      (libsource (lib "CommunityVault") (part "CMP-7833283-2"))
    )
    (comp (ref "R32")
      (value "Yageo AC0402JR-070RL")
      (footprint "RESC1005X37X25NL05T10")
      (description "RES SMD 0.0 OHM JUMPER 1/16W")
      (fields
        (field (name "MANUFACTURER PART NUMBER") "AC0402JR-070RL")
        (field (name "RESISTANCE") "0.0 Ω")
        (field (name "LCSC PART #") "C17168")
      )
      (libsource (lib "CommunityVault") (part "CMP-1900348-2"))
    )
    (comp (ref "R33")
      (value "Yageo AC0402JR-070RL")
      (footprint "RESC1005X37X25NL05T10")
      (description "RES SMD 0.0 OHM JUMPER 1/16W")
      (fields
        (field (name "MANUFACTURER PART NUMBER") "AC0402JR-070RL")
        (field (name "RESISTANCE") "0.0 Ω")
        (field (name "LCSC PART #") "C17168")
      )
      (libsource (lib "CommunityVault") (part "CMP-1900348-2"))
    )
    (comp (ref "R34")
      (value "Vishay Dale CRCW0603680KFKEA")
      (footprint "RESC1609X50X30NL10T20")
      (description "RES SMD 680K OHM 1% 1/10W 0603")
      (fields
        (field (name "CASE/PACKAGE") "0603")
        (field (name "RESISTANCE") "680kΩ")
        (field (name "MANUFACTURER PART NUMBER") "CRCW0603680KFKEA")
        (field (name "LCSC PART #") "C25822")
      )
      (libsource (lib "CommunityVault") (part "CMP-1873487-2"))
    )
    (comp (ref "R35")
      (value "Yageo AC0402FR-071ML")
      (footprint "RESC1005X37X25NL05T10")
      (description "Thick Film Resistors 1/16W 1M ohm 1%")
      (fields
        (field (name "MANUFACTURER PART NUMBER") "AC0402FR-071ML")
        (field (name "RESISTANCE") "1MΩ")
        (field (name "LCSC PART #") "C26083")
      )
      (libsource (lib "CommunityVault") (part "CMP-7833283-2"))
    )
    (comp (ref "R36")
      (value "Vishay Dale CRCW0402220RFKED")
      (footprint "RESC1005X40X25NL05T05")
      (description "RES SMD 220 OHM 1% 1/16W 0402")
      (fields
        (field (name "RESISTANCE") "220.0 Ω")
        (field (name "MANUFACTURER PART NUMBER") "CRCW0402220RFKED")
        (field (name "LCSC PART #") "C25091")
      )
      (libsource (lib "CommunityVault") (part "CMP-1867363-2"))
    )
    (comp (ref "R37")
      (value "Panasonic ERJ-U02F1001X")
      (footprint "RESC1005X40X25NL05T10")
      (description "Thick Film Resistors - SMD 0402 1% 1.0Kohm Anti-Sulfur")
      (fields
        (field (name "MANUFACTURER PART NUMBER") "ERJ-U02F1001X")
        (field (name "RESISTANCE") "1kΩ")
        (field (name "LCSC PART #") "C11702")
      )
      (libsource (lib "CommunityVault") (part "CMP-9105019-2"))
    )
    (comp (ref "SH1")
      (value "Leader Tech SMS-403C")
      (footprint "PCB-mz3zksww60jqn1djdwiu-1")
      (fields
        (field (name "MANUFACTURER PART NUMBER") "SMS-403C")
        (field (name "SIZE") "26.26 x 26.26x 2.0 mm")
      )
      (libsource (lib "CommunityVault") (part "CMP-da641787f57f05a3-1"))
    )
    (comp (ref "SW1")
      (value "TS-1185-C-A-A-A")
      (footprint "PCB-qarcnbrnejma51b9hfzm-1")
      (description "SPST 50mA @ 12VDC Vertical Round Button 260gf SMD Tactile Switches RoHS")
      (fields (field (name "LCSC PART #") "C561518") (field (name "MANUFACTURER") "XKB Connectivity"))
      (libsource (lib "FavoritesLibrary") (part "SYM-hgui3ccx9uakpoe7vbsx-1"))
    )
    (comp (ref "SW2")
      (value "TS-1185-C-A-A-A")
      (footprint "PCB-qarcnbrnejma51b9hfzm-1")
      (description "SPST 50mA @ 12VDC Vertical Round Button 260gf SMD Tactile Switches RoHS")
      (fields (field (name "LCSC PART #") "C561518") (field (name "MANUFACTURER") "XKB Connectivity"))
      (libsource (lib "FavoritesLibrary") (part "SYM-hgui3ccx9uakpoe7vbsx-1"))
    )
    (comp (ref "SW3")
      (value "JS202011AQN")
      (footprint "PCB-wbq3apgbd2bliremr4t3-1")
      (description "Switch Slide DPDT Side Slide 0.3A 30VDC PC Pins Thru-Hole Bulk")
      (fields (field (name "LCSC PART #") "C221662"))
      (libsource (lib "CommunityVault") (part "CMP-c7970ef1edec1850-5"))
    )
    (comp (ref "U1")
      (value "Espressif Systems ESP32-WROOM-32E")
      (footprint "ESP32-WROOM-32E")
      (description "Rx Txrx Mod Wifi Trace Ant SMD")
      (fields
        (field (name "MANUFACTURER PART NUMBER") "ESP32-WROOM-32E")
        (field (name "LCSC PART #") "C701341")
      )
      (libsource (lib "CommunityVault") (part "CMP-313bfeb3df46eefc-3"))
    )
    (comp (ref "U2")
      (value "TPS63000DRCRG4")
      (footprint "DRC10-2400X1650TP")
      (fields
        (field (name "MANUFACTURER PART NUMBER") "TPS63001DRCRG4")
        (field (name "LCSC PART #") "C24966")
      )
      (libsource (lib "CommunityVault") (part "CMP-1489379-3"))
    )
    (comp (ref "U3")
      (value "LM66100DCKR")
      (footprint "TSOP65P210X110-6N")
      (description "1.5-V to 5.5-V, 1.5-A, 0.5-uA IQ ideal diode with Integrated FET 6-SC70 -40 to 105")
      (libsource (lib "CommunityVault") (part "CMP-6f39a3c4d5dbb0fe-3"))
    )
    (comp (ref "U4")
      (value "Analog Devices AD5160BRJZ10-RL7")
      (footprint "TSOP65P280X145-8N")
      (description "Digital Potentiometer 10kOhm 256POS Volatile Linear Automotive 8-Pin SOT-23 T/R")
      (fields
        (field (name "MANUFACTURER PART NUMBER") "AD5160BRJZ10-RL7")
        (field (name "RESISTANCE") "10.0 kΩ")
        (field (name "LCSC PART #") "C40097")
      )
      (libsource (lib "CommunityVault") (part "CMP-6bc4a2c881d8b403-1"))
    )
    (comp (ref "U5")
      (value "REF1933AIDDCT")
      (footprint "SOT95P280X100-5N")
      (description "3.3-V Vref, dual-output Vref & Vref/2 voltage reference 5-SOT-23-THIN -40 to 125")
      (libsource (lib "FavoritesLibrary") (part "SYM-b2327839c6726df5-6"))
    )
    (comp (ref "U6")
      (value "MCP6002T-I/SN")
      (footprint "SOIC127P600X175-8N")
      (description "5MHz 15V/us High Slew-Rate RRIO Operational Amplifier 8-Pin SOIC T/R")
      (fields (field (name "MANUFACTURER PART NUMBER") "TLV9052IDR") (field (name "LCSC PART #") "C7377"))
      (libsource (lib "CommunityVault") (part "CMP-cf0503be886010c2-1"))
    )
    (comp (ref "U7")
      (value "INA126EA/2K5")
      (footprint "TI-DGK8_N")
      (libsource (lib "CommunityVault") (part "CMP-1215678-2"))
    )
    (comp (ref "U9")
      (value "MCP6002T-I/SN")
      (footprint "SOIC127P600X175-8N")
      (description "5MHz 15V/us High Slew-Rate RRIO Operational Amplifier 8-Pin SOIC T/R")
      (fields (field (name "MANUFACTURER PART NUMBER") "TLV9052IDR") (field (name "LCSC PART #") "C7377"))
      (libsource (lib "CommunityVault") (part "CMP-cf0503be886010c2-1"))
    )
    (comp (ref "U10")
      (value "MCP6002T-I/SN")
      (footprint "SOIC127P600X175-8N")
      (description "5MHz 15V/us High Slew-Rate RRIO Operational Amplifier 8-Pin SOIC T/R")
      (fields (field (name "MANUFACTURER PART NUMBER") "TLV9052IDR") (field (name "LCSC PART #") "C7377"))
      (libsource (lib "CommunityVault") (part "CMP-cf0503be886010c2-1"))
    )
  )
  (nets
    (net (code "1") (name "/ADC") (class "Default")
      (node (ref "C13") (pin "1") (pinfunction "1_1") (pintype "passive"))
      (node (ref "R21") (pin "2") (pinfunction "2_2") (pintype "passive"))
      (node (ref "U1") (pin "9") (pinfunction "IO33_9") (pintype "bidirectional"))
      (node (ref "U10") (pin "1") (pinfunction "OUT1_1") (pintype "output"))
    )
    (net (code "2") (name "/BOOT0") (class "Default")
      (node (ref "D7") (pin "1") (pinfunction "1_1") (pintype "passive"))
      (node (ref "U1") (pin "25") (pinfunction "IO0_25") (pintype "bidirectional"))
    )
    (net (code "3") (name "/BUT_A") (class "Default")
      (node (ref "C6") (pin "1") (pinfunction "1_1") (pintype "passive"))
      (node (ref "D1") (pin "2") (pinfunction "2_2") (pintype "passive"))
      (node (ref "R5") (pin "2") (pinfunction "2_2") (pintype "passive"))
      (node (ref "SW1") (pin "2") (pinfunction "2_2") (pintype "passive"))
      (node (ref "U1") (pin "8") (pinfunction "IO32_8") (pintype "bidirectional"))
    )
    (net (code "4") (name "/BUT_B") (class "Default")
      (node (ref "C34") (pin "1") (pinfunction "1_1") (pintype "passive"))
      (node (ref "D2") (pin "2") (pinfunction "2_2") (pintype "passive"))
      (node (ref "R27") (pin "2") (pinfunction "2_2") (pintype "passive"))
      (node (ref "SW2") (pin "2") (pinfunction "2_2") (pintype "passive"))
      (node (ref "U1") (pin "6") (pinfunction "IO34_6") (pintype "bidirectional"))
    )
    (net (code "5") (name "/CABLE_SCREEN") (class "Default")
      (node (ref "U6") (pin "1") (pinfunction "OUT1_1") (pintype "output"))
      (node (ref "U6") (pin "2") (pinfunction "IN1-_2") (pintype "passive"))
    )
    (net (code "6") (name "/CS_N") (class "Default")
      (node (ref "U1") (pin "29") (pinfunction "IO5_29") (pintype "bidirectional"))
      (node (ref "U4") (pin "6") (pinfunction "~{CS}_6") (pintype "input"))
    )
    (net (code "7") (name "/ELECTRODE_N") (class "Default")
      (node (ref "D4") (pin "2") (pinfunction "2_2") (pintype "passive"))
      (node (ref "R13") (pin "2") (pinfunction "2_2") (pintype "passive"))
    )
    (net (code "8") (name "/ELECTRODE_P") (class "Default")
      (node (ref "D5") (pin "2") (pinfunction "2_2") (pintype "passive"))
      (node (ref "R17") (pin "2") (pinfunction "2_2") (pintype "passive"))
    )
    (net (code "9") (name "/ELECTRODE_RLD") (class "Default")
      (node (ref "D3") (pin "2") (pinfunction "2_2") (pintype "passive"))
      (node (ref "R24") (pin "1") (pinfunction "1_1") (pintype "passive"))
    )
    (net (code "10") (name "/ESP32_EN") (class "Default")
      (node (ref "C1") (pin "1") (pinfunction "1_1") (pintype "passive"))
      (node (ref "D8") (pin "1") (pinfunction "1_1") (pintype "passive"))
      (node (ref "R1") (pin "2") (pinfunction "2_2") (pintype "passive"))
      (node (ref "U1") (pin "3") (pinfunction "EN_3") (pintype "input"))
    )
    (net (code "11") (name "/ESP32_RX") (class "Default")
      (node (ref "D10") (pin "1") (pinfunction "1_1") (pintype "passive"))
      (node (ref "U1") (pin "34") (pinfunction "RXD0_34") (pintype "input"))
    )
    (net (code "12") (name "/ESP32_TX") (class "Default")
      (node (ref "D9") (pin "1") (pinfunction "1_1") (pintype "passive"))
      (node (ref "U1") (pin "35") (pinfunction "TXD0_35") (pintype "output"))
    )
    (net (code "13") (name "/FILTER_OUT") (class "Default")
      (node (ref "C14") (pin "2") (pinfunction "2_2") (pintype "passive"))
      (node (ref "C15") (pin "1") (pinfunction "1_1") (pintype "passive"))
      (node (ref "R16") (pin "2") (pinfunction "2_2") (pintype "passive"))
      (node (ref "R20") (pin "1") (pinfunction "1_1") (pintype "passive"))
      (node (ref "U10") (pin "7") (pinfunction "OUT1_7") (pintype "passive"))
    )
    (net (code "14") (name "/GRN_LED") (class "Default")
      (node (ref "R36") (pin "2") (pinfunction "2_2") (pintype "passive"))
      (node (ref "U1") (pin "11") (pinfunction "IO26_11") (pintype "bidirectional"))
    )
    (net (code "15") (name "/INAMP_OUT") (class "Default")
      (node (ref "C27") (pin "1") (pinfunction "1_1") (pintype "passive"))
      (node (ref "C30") (pin "1") (pinfunction "1_1") (pintype "passive"))
      (node (ref "R14") (pin "1") (pinfunction "1_1") (pintype "passive"))
      (node (ref "R18") (pin "2") (pinfunction "2_2") (pintype "passive"))
      (node (ref "R19") (pin "2") (pinfunction "2_2") (pintype "passive"))
      (node (ref "U7") (pin "6") (pinfunction "VO_6") (pintype "output"))
    )
    (net (code "16") (name "/MISO") (class "Default")
      (node (ref "U1") (pin "31") (pinfunction "IO19_31") (pintype "bidirectional"))
    )
    (net (code "17") (name "/MOSI") (class "Default")
      (node (ref "U1") (pin "37") (pinfunction "IO23_37") (pintype "bidirectional"))
      (node (ref "U4") (pin "5") (pinfunction "SDI_5") (pintype "input"))
    )
    (net (code "18") (name "/PA0") (class "Default")
      (node (ref "R23") (pin "1") (pinfunction "1_1") (pintype "passive"))
      (node (ref "R8") (pin "1") (pinfunction "1_1") (pintype "passive"))
      (node (ref "U4") (pin "8") (pinfunction "A_8") (pintype "passive"))
    )
    (net (code "19") (name "/PB0") (class "Default")
      (node (ref "R21") (pin "1") (pinfunction "1_1") (pintype "passive"))
      (node (ref "R26") (pin "1") (pinfunction "1_1") (pintype "passive"))
      (node (ref "U4") (pin "7") (pinfunction "B_7") (pintype "passive"))
    )
    (net (code "20") (name "/PW0") (class "Default")
      (node (ref "C13") (pin "2") (pinfunction "2_2") (pintype "passive"))
      (node (ref "R23") (pin "2") (pinfunction "2_2") (pintype "passive"))
      (node (ref "R26") (pin "2") (pinfunction "2_2") (pintype "passive"))
      (node (ref "U10") (pin "2") (pinfunction "IN1-_2") (pintype "passive"))
      (node (ref "U4") (pin "1") (pinfunction "W_1") (pintype "passive"))
    )
    (net (code "21") (name "/RED_LED") (class "Default")
      (node (ref "R37") (pin "2") (pinfunction "2_2") (pintype "passive"))
      (node (ref "U1") (pin "16") (pinfunction "IO13_16") (pintype "bidirectional"))
    )
    (net (code "22") (name "/RG1") (class "Default")
      (node (ref "R29") (pin "1") (pinfunction "1_1") (pintype "passive"))
      (node (ref "R7") (pin "1") (pinfunction "1_1") (pintype "passive"))
      (node (ref "U7") (pin "1") (pinfunction "RG_1") (pintype "input"))
    )
    (net (code "23") (name "/RG2") (class "Default")
      (node (ref "R29") (pin "2") (pinfunction "2_2") (pintype "passive"))
      (node (ref "R9") (pin "2") (pinfunction "2_2") (pintype "passive"))
      (node (ref "U7") (pin "8") (pinfunction "RG_8") (pintype "input"))
    )
    (net (code "24") (name "/RLD_BUF") (class "Default")
      (node (ref "R22") (pin "2") (pinfunction "2_2") (pintype "passive"))
      (node (ref "U9") (pin "1") (pinfunction "OUT1_1") (pintype "output"))
      (node (ref "U9") (pin "2") (pinfunction "IN1-_2") (pintype "passive"))
    )
    (net (code "25") (name "/SCK") (class "Default")
      (node (ref "U1") (pin "30") (pinfunction "IO18_30") (pintype "bidirectional"))
      (node (ref "U4") (pin "4") (pinfunction "CLK_4") (pintype "input"))
    )
    (net (code "26") (name "/VBATT_MON") (class "Default")
      (node (ref "C36") (pin "1") (pinfunction "1_1") (pintype "passive"))
      (node (ref "R34") (pin "2") (pinfunction "2_2") (pintype "passive"))
      (node (ref "R35") (pin "1") (pinfunction "1_1") (pintype "passive"))
      (node (ref "U1") (pin "7") (pinfunction "IO35_7") (pintype "bidirectional"))
    )
    (net (code "27") (name "/VFB") (class "Default")
      (node (ref "C4") (pin "2") (pinfunction "2_2") (pintype "passive"))
      (node (ref "R2") (pin "2") (pinfunction "2_2") (pintype "passive"))
      (node (ref "R3") (pin "1") (pinfunction "1_1") (pintype "passive"))
      (node (ref "U2") (pin "10") (pinfunction "FB_10") (pintype "input"))
    )
    (net (code "28") (name "/VREF") (class "Default")
      (node (ref "C18") (pin "1") (pinfunction "1_1") (pintype "passive"))
      (node (ref "C24") (pin "1") (pinfunction "1_1") (pintype "passive"))
      (node (ref "C25") (pin "1") (pinfunction "1_1") (pintype "passive"))
      (node (ref "C26") (pin "1") (pinfunction "1_1") (pintype "passive"))
      (node (ref "C28") (pin "2") (pinfunction "2_2") (pintype "passive"))
      (node (ref "C29") (pin "2") (pinfunction "2_2") (pintype "passive"))
      (node (ref "R10") (pin "1") (pinfunction "1_1") (pintype "passive"))
      (node (ref "R11") (pin "1") (pinfunction "1_1") (pintype "passive"))
      (node (ref "R12") (pin "1") (pinfunction "1_1") (pintype "passive"))
      (node (ref "R25") (pin "1") (pinfunction "1_1") (pintype "passive"))
      (node (ref "R28") (pin "2") (pinfunction "2_2") (pintype "passive"))
      (node (ref "R33") (pin "1") (pinfunction "1_1") (pintype "passive"))
      (node (ref "R8") (pin "2") (pinfunction "2_2") (pintype "passive"))
      (node (ref "U6") (pin "5") (pinfunction "IN2+_5") (pintype "passive"))
      (node (ref "U9") (pin "5") (pinfunction "IN2+_5") (pintype "passive"))
    )
    (net (code "29") (name "3V3") (class "Default")
      (node (ref "C21") (pin "1") (pinfunction "1_1") (pintype "passive"))
      (node (ref "C22") (pin "1") (pinfunction "1_1") (pintype "passive"))
      (node (ref "C4") (pin "1") (pinfunction "1_1") (pintype "passive"))
      (node (ref "C5") (pin "1") (pinfunction "1_1") (pintype "passive"))
      (node (ref "FB1") (pin "1") (pinfunction "1_1") (pintype "passive"))
      (node (ref "R27") (pin "1") (pinfunction "1_1") (pintype "passive"))
      (node (ref "R3") (pin "2") (pinfunction "2_2") (pintype "passive"))
      (node (ref "R5") (pin "1") (pinfunction "1_1") (pintype "passive"))
      (node (ref "U2") (pin "1") (pinfunction "VOUT_1") (pintype "power_in"))
      (node (ref "U5") (pin "3") (pinfunction "EN_3") (pintype "input"))
      (node (ref "U5") (pin "4") (pinfunction "VIN_4") (pintype "power_in"))
    )
    (net (code "30") (name "DBG_PWR") (class "Default")
      (node (ref "SW3") (pin "3") (pinfunction "3_3") (pintype "passive"))
      (node (ref "SW3") (pin "6") (pinfunction "6_6") (pintype "passive"))
    )
    (net (code "31") (name "DVDD") (class "Default")
      (node (ref "C2") (pin "1") (pinfunction "1_1") (pintype "passive"))
      (node (ref "C3") (pin "1") (pinfunction "1_1") (pintype "passive"))
      (node (ref "FB1") (pin "2") (pinfunction "2_2") (pintype "passive"))
      (node (ref "R1") (pin "1") (pinfunction "1_1") (pintype "passive"))
      (node (ref "U1") (pin "2") (pinfunction "3V3_2") (pintype "power_in"))
    )
    (net (code "32") (name "GND") (class "Default")
      (node (ref "C1") (pin "2") (pinfunction "2_2") (pintype "passive"))
      (node (ref "C10") (pin "2") (pinfunction "2_2") (pintype "passive"))
      (node (ref "C11") (pin "2") (pinfunction "2_2") (pintype "passive"))
      (node (ref "C12") (pin "2") (pinfunction "2_2") (pintype "passive"))
      (node (ref "C2") (pin "2") (pinfunction "2_2") (pintype "passive"))
      (node (ref "C21") (pin "2") (pinfunction "2_2") (pintype "passive"))
      (node (ref "C22") (pin "2") (pinfunction "2_2") (pintype "passive"))
      (node (ref "C23") (pin "2") (pinfunction "2_2") (pintype "passive"))
      (node (ref "C24") (pin "2") (pinfunction "2_2") (pintype "passive"))
      (node (ref "C3") (pin "2") (pinfunction "2_2") (pintype "passive"))
      (node (ref "C32") (pin "2") (pinfunction "2_2") (pintype "passive"))
      (node (ref "C33") (pin "2") (pinfunction "2_2") (pintype "passive"))
      (node (ref "C34") (pin "2") (pinfunction "2_2") (pintype "passive"))
      (node (ref "C35") (pin "2") (pinfunction "2_2") (pintype "passive"))
      (node (ref "C36") (pin "2") (pinfunction "2_2") (pintype "passive"))
      (node (ref "C5") (pin "2") (pinfunction "2_2") (pintype "passive"))
      (node (ref "C6") (pin "2") (pinfunction "2_2") (pintype "passive"))
      (node (ref "C7") (pin "2") (pinfunction "2_2") (pintype "passive"))
      (node (ref "C8") (pin "2") (pinfunction "2_2") (pintype "passive"))
      (node (ref "C9") (pin "2") (pinfunction "2_2") (pintype "passive"))
      (node (ref "D1") (pin "1") (pinfunction "1_1") (pintype "passive"))
      (node (ref "D10") (pin "2") (pinfunction "2_2") (pintype "passive"))
      (node (ref "D11") (pin "2") (pinfunction "K_2") (pintype "passive"))
      (node (ref "D12") (pin "2") (pinfunction "K_2") (pintype "passive"))
      (node (ref "D2") (pin "1") (pinfunction "1_1") (pintype "passive"))
      (node (ref "D3") (pin "1") (pinfunction "1_1") (pintype "passive"))
      (node (ref "D4") (pin "1") (pinfunction "1_1") (pintype "passive"))
      (node (ref "D5") (pin "1") (pinfunction "1_1") (pintype "passive"))
      (node (ref "D6") (pin "1") (pinfunction "1_1") (pintype "passive"))
      (node (ref "D7") (pin "2") (pinfunction "2_2") (pintype "passive"))
      (node (ref "D8") (pin "2") (pinfunction "2_2") (pintype "passive"))
      (node (ref "D9") (pin "2") (pinfunction "2_2") (pintype "passive"))
      (node (ref "P1") (pin "2") (pinfunction "1_2") (pintype "passive"))
      (node (ref "R2") (pin "1") (pinfunction "1_1") (pintype "passive"))
      (node (ref "R30") (pin "1") (pinfunction "1_1") (pintype "passive"))
      (node (ref "R35") (pin "2") (pinfunction "2_2") (pintype "passive"))
      (node (ref "SH1") (pin "1") (pintype "passive"))
      (node (ref "SW1") (pin "1") (pinfunction "1_1") (pintype "passive"))
      (node (ref "SW2") (pin "1") (pinfunction "1_1") (pintype "passive"))
      (node (ref "U1") (pin "1") (pinfunction "GND_1") (pintype "power_in"))
      (node (ref "U1") (pin "15") (pinfunction "GND_15") (pintype "power_in"))
      (node (ref "U1") (pin "38") (pinfunction "GND_38") (pintype "power_in"))
      (node (ref "U1") (pin "39") (pinfunction "EPAD_39") (pintype "power_in"))
      (node (ref "U10") (pin "4") (pinfunction "V-_4") (pintype "power_in"))
      (node (ref "U2") (pin "11") (pinfunction "EP_11") (pintype "power_in"))
      (node (ref "U2") (pin "3") (pinfunction "PGND_3") (pintype "power_in"))
      (node (ref "U2") (pin "9") (pinfunction "GND_9") (pintype "power_in"))
      (node (ref "U3") (pin "2") (pinfunction "GND_2") (pintype "passive"))
      (node (ref "U3") (pin "3") (pinfunction "~{CE}_3") (pintype "input"))
      (node (ref "U3") (pin "5") (pinfunction "ST_5") (pintype "passive"))
      (node (ref "U4") (pin "3") (pinfunction "GND_3") (pintype "power_in"))
      (node (ref "U5") (pin "2") (pinfunction "GND_2") (pintype "power_in"))
      (node (ref "U6") (pin "4") (pinfunction "V-_4") (pintype "power_in"))
      (node (ref "U7") (pin "4") (pinfunction "V-_4") (pintype "power_in"))
      (node (ref "U9") (pin "4") (pinfunction "V-_4") (pintype "power_in"))
    )
    (net (code "33") (name "Net-(C14-Pad1)") (class "Default")
      (node (ref "C14") (pin "1") (pinfunction "1_1") (pintype "passive"))
      (node (ref "C15") (pin "2") (pinfunction "2_2") (pintype "passive"))
      (node (ref "R10") (pin "2") (pinfunction "2_2") (pintype "passive"))
      (node (ref "R14") (pin "2") (pinfunction "2_2") (pintype "passive"))
      (node (ref "R15") (pin "1") (pinfunction "1_1") (pintype "passive"))
    )
    (net (code "34") (name "Net-(C16-Pad1)") (class "Default")
      (node (ref "C16") (pin "1") (pinfunction "1_1") (pintype "passive"))
      (node (ref "C19") (pin "2") (pinfunction "2_2") (pintype "passive"))
      (node (ref "C28") (pin "1") (pinfunction "1_1") (pintype "passive"))
      (node (ref "R13") (pin "1") (pinfunction "1_1") (pintype "passive"))
    )
    (net (code "35") (name "Net-(C19-Pad1)") (class "Default")
      (node (ref "C19") (pin "1") (pinfunction "1_1") (pintype "passive"))
      (node (ref "C20") (pin "2") (pinfunction "2_2") (pintype "passive"))
      (node (ref "C29") (pin "1") (pinfunction "1_1") (pintype "passive"))
      (node (ref "R17") (pin "1") (pinfunction "1_1") (pintype "passive"))
    )
    (net (code "36") (name "Net-(D11-A)") (class "Default")
      (node (ref "D11") (pin "1") (pinfunction "A_1") (pintype "passive"))
      (node (ref "R36") (pin "1") (pinfunction "1_1") (pintype "passive"))
    )
    (net (code "37") (name "Net-(D12-A)") (class "Default")
      (node (ref "D12") (pin "1") (pinfunction "A_1") (pintype "passive"))
      (node (ref "R37") (pin "1") (pinfunction "1_1") (pintype "passive"))
    )
    (net (code "38") (name "Net-(U2-EN)") (class "Default")
      (node (ref "C8") (pin "1") (pinfunction "1_1") (pintype "passive"))
      (node (ref "R6") (pin "1") (pinfunction "1_1") (pintype "passive"))
      (node (ref "U2") (pin "6") (pinfunction "EN_6") (pintype "input"))
      (node (ref "U2") (pin "7") (pinfunction "PS/SYNC_7") (pintype "input"))
      (node (ref "U2") (pin "8") (pinfunction "VINA_8") (pintype "power_in"))
    )
    (net (code "39") (name "Net-(U2-L1)") (class "Default")
      (node (ref "L1") (pin "1") (pinfunction "1_1") (pintype "passive"))
      (node (ref "U2") (pin "4") (pinfunction "L1_4") (pintype "passive"))
    )
    (net (code "40") (name "Net-(U2-L2)") (class "Default")
      (node (ref "L1") (pin "2") (pinfunction "2_2") (pintype "passive"))
      (node (ref "U2") (pin "2") (pinfunction "L2_2") (pintype "passive"))
    )
    (net (code "41") (name "Net-(U3-VIN)") (class "Default")
      (node (ref "D6") (pin "2") (pinfunction "2_2") (pintype "passive"))
      (node (ref "SW3") (pin "2") (pinfunction "2_2") (pintype "passive"))
      (node (ref "SW3") (pin "5") (pinfunction "5_5") (pintype "passive"))
      (node (ref "U3") (pin "1") (pinfunction "VIN_1") (pintype "power_in"))
    )
    (net (code "42") (name "Net-(U5-VBIAS)") (class "Default")
      (node (ref "R33") (pin "2") (pinfunction "2_2") (pintype "passive"))
      (node (ref "U5") (pin "1") (pinfunction "VBIAS_1") (pintype "passive"))
    )
    (net (code "43") (name "Net-(U5-VREF)") (class "Default")
      (node (ref "R32") (pin "2") (pinfunction "2_2") (pintype "passive"))
      (node (ref "U5") (pin "5") (pinfunction "VREF_5") (pintype "power_in"))
    )
    (net (code "44") (name "Net-(U6A-IN1+)") (class "Default")
      (node (ref "C35") (pin "1") (pinfunction "1_1") (pintype "passive"))
      (node (ref "R28") (pin "1") (pinfunction "1_1") (pintype "passive"))
      (node (ref "R30") (pin "2") (pinfunction "2_2") (pintype "passive"))
      (node (ref "U6") (pin "3") (pinfunction "IN1+_3") (pintype "passive"))
    )
    (net (code "45") (name "Net-(U6B-IN2-)") (class "Default")
      (node (ref "C17") (pin "1") (pinfunction "1_1") (pintype "passive"))
      (node (ref "R19") (pin "1") (pinfunction "1_1") (pintype "passive"))
      (node (ref "U6") (pin "6") (pinfunction "IN2-_6") (pintype "passive"))
    )
    (net (code "46") (name "Net-(U6B-OUT1)") (class "Default")
      (node (ref "C17") (pin "2") (pinfunction "2_2") (pintype "passive"))
      (node (ref "U6") (pin "7") (pinfunction "OUT1_7") (pintype "passive"))
      (node (ref "U7") (pin "5") (pinfunction "REF_5") (pintype "input"))
    )
    (net (code "47") (name "Net-(U7-VIN+)") (class "Default")
      (node (ref "C20") (pin "1") (pinfunction "1_1") (pintype "passive"))
      (node (ref "R12") (pin "2") (pinfunction "2_2") (pintype "passive"))
      (node (ref "U7") (pin "3") (pinfunction "VIN+_3") (pintype "input"))
    )
    (net (code "48") (name "Net-(U7-VIN-)") (class "Default")
      (node (ref "C16") (pin "2") (pinfunction "2_2") (pintype "passive"))
      (node (ref "R11") (pin "2") (pinfunction "2_2") (pintype "passive"))
      (node (ref "U7") (pin "2") (pinfunction "VIN-_2") (pintype "input"))
    )
    (net (code "49") (name "Net-(U9A-IN1+)") (class "Default")
      (node (ref "R7") (pin "2") (pinfunction "2_2") (pintype "passive"))
      (node (ref "R9") (pin "1") (pinfunction "1_1") (pintype "passive"))
      (node (ref "U9") (pin "3") (pinfunction "IN1+_3") (pintype "passive"))
    )
    (net (code "50") (name "Net-(U9B-IN2-)") (class "Default")
      (node (ref "C31") (pin "2") (pinfunction "2_2") (pintype "passive"))
      (node (ref "R22") (pin "1") (pinfunction "1_1") (pintype "passive"))
      (node (ref "R31") (pin "1") (pinfunction "1_1") (pintype "passive"))
      (node (ref "U9") (pin "6") (pinfunction "IN2-_6") (pintype "passive"))
    )
    (net (code "51") (name "Net-(U9B-OUT1)") (class "Default")
      (node (ref "C31") (pin "1") (pinfunction "1_1") (pintype "passive"))
      (node (ref "R24") (pin "2") (pinfunction "2_2") (pintype "passive"))
      (node (ref "R31") (pin "2") (pinfunction "2_2") (pintype "passive"))
      (node (ref "U9") (pin "7") (pinfunction "OUT1_7") (pintype "passive"))
    )
    (net (code "52") (name "Net-(U10A-IN1+)") (class "Default")
      (node (ref "C25") (pin "2") (pinfunction "2_2") (pintype "passive"))
      (node (ref "C26") (pin "2") (pinfunction "2_2") (pintype "passive"))
      (node (ref "R16") (pin "1") (pinfunction "1_1") (pintype "passive"))
      (node (ref "U10") (pin "3") (pinfunction "IN1+_3") (pintype "passive"))
    )
    (net (code "53") (name "Net-(U10B-IN2+)") (class "Default")
      (node (ref "C18") (pin "2") (pinfunction "2_2") (pintype "passive"))
      (node (ref "C27") (pin "2") (pinfunction "2_2") (pintype "passive"))
      (node (ref "C30") (pin "2") (pinfunction "2_2") (pintype "passive"))
      (node (ref "R15") (pin "2") (pinfunction "2_2") (pintype "passive"))
      (node (ref "U10") (pin "5") (pinfunction "IN2+_5") (pintype "passive"))
    )
    (net (code "54") (name "Net-(U10B-IN2-)") (class "Default")
      (node (ref "R18") (pin "1") (pinfunction "1_1") (pintype "passive"))
      (node (ref "R20") (pin "2") (pinfunction "2_2") (pintype "passive"))
      (node (ref "R25") (pin "2") (pinfunction "2_2") (pintype "passive"))
      (node (ref "U10") (pin "6") (pinfunction "IN2-_6") (pintype "passive"))
    )
    (net (code "55") (name "VBATT") (class "Default")
      (node (ref "P1") (pin "1") (pinfunction "1_1") (pintype "passive"))
      (node (ref "SW3") (pin "1") (pinfunction "1_1") (pintype "passive"))
      (node (ref "SW3") (pin "4") (pinfunction "4_4") (pintype "passive"))
    )
    (net (code "56") (name "VBATT_SW") (class "Default")
      (node (ref "C32") (pin "1") (pinfunction "1_1") (pintype "passive"))
      (node (ref "C7") (pin "1") (pinfunction "1_1") (pintype "passive"))
      (node (ref "R34") (pin "1") (pinfunction "1_1") (pintype "passive"))
      (node (ref "R6") (pin "2") (pinfunction "2_2") (pintype "passive"))
      (node (ref "U2") (pin "5") (pinfunction "VIN_5") (pintype "power_in"))
      (node (ref "U3") (pin "6") (pinfunction "VOUT_6") (pintype "power_in"))
    )
    (net (code "57") (name "VCC") (class "Default")
      (node (ref "C10") (pin "1") (pinfunction "1_1") (pintype "passive"))
      (node (ref "C11") (pin "1") (pinfunction "1_1") (pintype "passive"))
      (node (ref "C12") (pin "1") (pinfunction "1_1") (pintype "passive"))
      (node (ref "C23") (pin "1") (pinfunction "1_1") (pintype "passive"))
      (node (ref "C33") (pin "1") (pinfunction "1_1") (pintype "passive"))
      (node (ref "C9") (pin "1") (pinfunction "1_1") (pintype "passive"))
      (node (ref "R32") (pin "1") (pinfunction "1_1") (pintype "passive"))
      (node (ref "U10") (pin "8") (pinfunction "V+_8") (pintype "power_in"))
      (node (ref "U4") (pin "2") (pinfunction "VDD_2") (pintype "power_in"))
      (node (ref "U6") (pin "8") (pinfunction "V+_8") (pintype "power_in"))
      (node (ref "U7") (pin "7") (pinfunction "V+_7") (pintype "power_in"))
      (node (ref "U9") (pin "8") (pinfunction "V+_8") (pintype "power_in"))
    )
    (net (code "58") (name "unconnected-(U1-IO2-Pad24)") (class "Default")
      (node (ref "U1") (pin "24") (pinfunction "IO2_24") (pintype "bidirectional+no_connect"))
    )
    (net (code "59") (name "unconnected-(U1-IO4-Pad26)") (class "Default")
      (node (ref "U1") (pin "26") (pinfunction "IO4_26") (pintype "bidirectional+no_connect"))
    )
    (net (code "60") (name "unconnected-(U1-IO12-Pad14)") (class "Default")
      (node (ref "U1") (pin "14") (pinfunction "IO12_14") (pintype "bidirectional+no_connect"))
    )
    (net (code "61") (name "unconnected-(U1-IO14-Pad13)") (class "Default")
      (node (ref "U1") (pin "13") (pinfunction "IO14_13") (pintype "bidirectional+no_connect"))
    )
    (net (code "62") (name "unconnected-(U1-IO15-Pad23)") (class "Default")
      (node (ref "U1") (pin "23") (pinfunction "IO15_23") (pintype "bidirectional+no_connect"))
    )
    (net (code "63") (name "unconnected-(U1-IO16-Pad27)") (class "Default")
      (node (ref "U1") (pin "27") (pinfunction "IO16_27") (pintype "bidirectional+no_connect"))
    )
    (net (code "64") (name "unconnected-(U1-IO17-Pad28)") (class "Default")
      (node (ref "U1") (pin "28") (pinfunction "IO17_28") (pintype "bidirectional+no_connect"))
    )
    (net (code "65") (name "unconnected-(U1-IO21-Pad33)") (class "Default")
      (node (ref "U1") (pin "33") (pinfunction "IO21_33") (pintype "bidirectional+no_connect"))
    )
    (net (code "66") (name "unconnected-(U1-IO22-Pad36)") (class "Default")
      (node (ref "U1") (pin "36") (pinfunction "IO22_36") (pintype "bidirectional+no_connect"))
    )
    (net (code "67") (name "unconnected-(U1-IO25-Pad10)") (class "Default")
      (node (ref "U1") (pin "10") (pinfunction "IO25_10") (pintype "bidirectional+no_connect"))
    )
    (net (code "68") (name "unconnected-(U1-IO27-Pad12)") (class "Default")
      (node (ref "U1") (pin "12") (pinfunction "IO27_12") (pintype "bidirectional+no_connect"))
    )
    (net (code "69") (name "unconnected-(U1-NC-Pad17)") (class "Default")
      (node (ref "U1") (pin "17") (pinfunction "NC_17") (pintype "passive"))
    )
    (net (code "70") (name "unconnected-(U1-NC-Pad18)") (class "Default")
      (node (ref "U1") (pin "18") (pinfunction "NC_18") (pintype "passive"))
    )
    (net (code "71") (name "unconnected-(U1-NC-Pad19)") (class "Default")
      (node (ref "U1") (pin "19") (pinfunction "NC_19") (pintype "passive"))
    )
    (net (code "72") (name "unconnected-(U1-NC-Pad20)") (class "Default")
      (node (ref "U1") (pin "20") (pinfunction "NC_20") (pintype "passive"))
    )
    (net (code "73") (name "unconnected-(U1-NC-Pad21)") (class "Default")
      (node (ref "U1") (pin "21") (pinfunction "NC_21") (pintype "passive"))
    )
    (net (code "74") (name "unconnected-(U1-NC-Pad22)") (class "Default")
      (node (ref "U1") (pin "22") (pinfunction "NC_22") (pintype "passive"))
    )
    (net (code "75") (name "unconnected-(U1-NC-Pad32)") (class "Default")
      (node (ref "U1") (pin "32") (pinfunction "NC_32") (pintype "passive+no_connect"))
    )
    (net (code "76") (name "unconnected-(U1-SENSOR_VN-Pad5)") (class "Default")
      (node (ref "U1") (pin "5") (pinfunction "SENSOR_VN_5") (pintype "bidirectional+no_connect"))
    )
    (net (code "77") (name "unconnected-(U1-SENSOR_VP-Pad4)") (class "Default")
      (node (ref "U1") (pin "4") (pinfunction "SENSOR_VP_4") (pintype "bidirectional+no_connect"))
    )
  )
)
